# PCB-TLY-JACK-LEDS.net
KiCad netlist of a schematic drawn in EAGLE
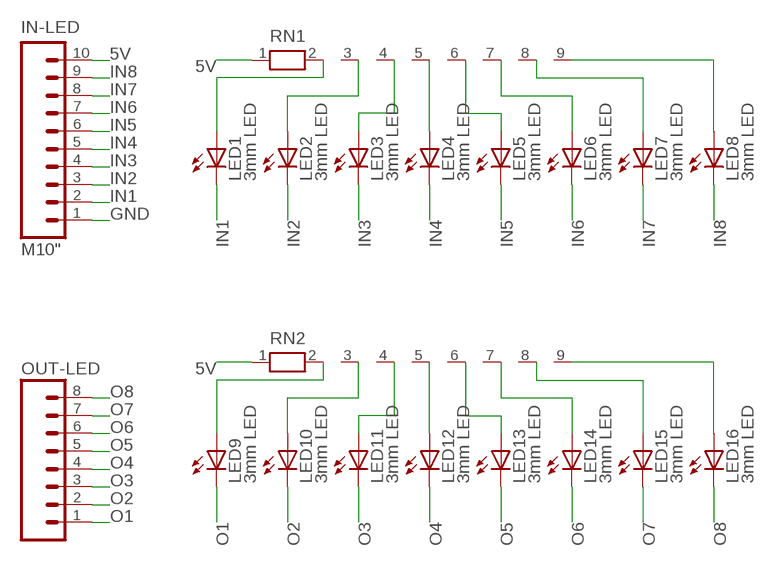
[diagram p0: schematic, sheet 1]

(export (version "E")
  (design (tool "Eeschema 10.0.6"))
  (components
    (comp (ref "IN-LED")
      (value "M10\"")
      (footprint "eagle-import:1X10")
      (libsource (lib "eagle-import") (part "M10{dblquote}"))
    )
    (comp (ref "LED1")
      (value "3mm LED")
      (footprint "eagle-import:LED3MM")
      (libsource (lib "eagle-import") (part "LED3MM"))
    )
    (comp (ref "LED2")
      (value "3mm LED")
      (footprint "eagle-import:LED3MM")
      (libsource (lib "eagle-import") (part "LED3MM"))
    )
    (comp (ref "LED3")
      (value "3mm LED")
      (footprint "eagle-import:LED3MM")
      (libsource (lib "eagle-import") (part "LED3MM"))
    )
    (comp (ref "LED4")
      (value "3mm LED")
      (footprint "eagle-import:LED3MM")
      (libsource (lib "eagle-import") (part "LED3MM"))
    )
    (comp (ref "LED5")
      (value "3mm LED")
      (footprint "eagle-import:LED3MM")
      (libsource (lib "eagle-import") (part "LED3MM"))
    )
    (comp (ref "LED6")
      (value "3mm LED")
      (footprint "eagle-import:LED3MM")
      (libsource (lib "eagle-import") (part "LED3MM"))
    )
    (comp (ref "LED7")
      (value "3mm LED")
      (footprint "eagle-import:LED3MM")
      (libsource (lib "eagle-import") (part "LED3MM"))
    )
    (comp (ref "LED8")
      (value "3mm LED")
      (footprint "eagle-import:LED3MM")
      (libsource (lib "eagle-import") (part "LED3MM"))
    )
    (comp (ref "LED9")
      (value "3mm LED")
      (footprint "eagle-import:LED3MM")
      (libsource (lib "eagle-import") (part "LED3MM"))
    )
    (comp (ref "LED10")
      (value "3mm LED")
      (footprint "eagle-import:LED3MM")
      (libsource (lib "eagle-import") (part "LED3MM"))
    )
    (comp (ref "LED11")
      (value "3mm LED")
      (footprint "eagle-import:LED3MM")
      (libsource (lib "eagle-import") (part "LED3MM"))
    )
    (comp (ref "LED12")
      (value "3mm LED")
      (footprint "eagle-import:LED3MM")
      (libsource (lib "eagle-import") (part "LED3MM"))
    )
    (comp (ref "LED13")
      (value "3mm LED")
      (footprint "eagle-import:LED3MM")
      (libsource (lib "eagle-import") (part "LED3MM"))
    )
    (comp (ref "LED14")
      (value "3mm LED")
      (footprint "eagle-import:LED3MM")
      (libsource (lib "eagle-import") (part "LED3MM"))
    )
    (comp (ref "LED15")
      (value "3mm LED")
      (footprint "eagle-import:LED3MM")
      (libsource (lib "eagle-import") (part "LED3MM"))
    )
    (comp (ref "LED16")
      (value "3mm LED")
      (footprint "eagle-import:LED3MM")
      (libsource (lib "eagle-import") (part "LED3MM"))
    )
    (comp (ref "OUT-LED")
      (value "M081X08")
      (footprint "eagle-import:1X08")
      (libsource (lib "eagle-import") (part "M081X08"))
    )
    (comp (ref "RN1")
      (value "RN08")
      (footprint "eagle-import:RN-9")
      (libsource (lib "eagle-import") (part "RN08"))
    )
    (comp (ref "RN2")
      (value "RN08")
      (footprint "eagle-import:RN-9")
      (libsource (lib "eagle-import") (part "RN08"))
    )
  )
  (nets
    (net (code "1") (name "/5V") (class "Default")
      (node (ref "IN-LED") (pin "10") (pinfunction "10_10") (pintype "passive"))
      (node (ref "RN1") (pin "1") (pinfunction "1_1") (pintype "passive"))
      (node (ref "RN2") (pin "1") (pinfunction "1_1") (pintype "passive"))
    )
    (net (code "2") (name "/GND") (class "Default")
      (node (ref "IN-LED") (pin "1") (pinfunction "1_1") (pintype "passive"))
    )
    (net (code "3") (name "/IN1") (class "Default")
      (node (ref "IN-LED") (pin "2") (pinfunction "2_2") (pintype "passive"))
      (node (ref "LED1") (pin "K") (pinfunction "C_K") (pintype "passive"))
    )
    (net (code "4") (name "/IN2") (class "Default")
      (node (ref "IN-LED") (pin "3") (pinfunction "3_3") (pintype "passive"))
      (node (ref "LED2") (pin "K") (pinfunction "C_K") (pintype "passive"))
    )
    (net (code "5") (name "/IN3") (class "Default")
      (node (ref "IN-LED") (pin "4") (pinfunction "4_4") (pintype "passive"))
      (node (ref "LED3") (pin "K") (pinfunction "C_K") (pintype "passive"))
    )
    (net (code "6") (name "/IN4") (class "Default")
      (node (ref "IN-LED") (pin "5") (pinfunction "5_5") (pintype "passive"))
      (node (ref "LED4") (pin "K") (pinfunction "C_K") (pintype "passive"))
    )
    (net (code "7") (name "/IN5") (class "Default")
      (node (ref "IN-LED") (pin "6") (pinfunction "6_6") (pintype "passive"))
      (node (ref "LED5") (pin "K") (pinfunction "C_K") (pintype "passive"))
    )
    (net (code "8") (name "/IN6") (class "Default")
      (node (ref "IN-LED") (pin "7") (pinfunction "7_7") (pintype "passive"))
      (node (ref "LED6") (pin "K") (pinfunction "C_K") (pintype "passive"))
    )
    (net (code "9") (name "/IN7") (class "Default")
      (node (ref "IN-LED") (pin "8") (pinfunction "8_8") (pintype "passive"))
      (node (ref "LED7") (pin "K") (pinfunction "C_K") (pintype "passive"))
    )
    (net (code "10") (name "/IN8") (class "Default")
      (node (ref "IN-LED") (pin "9") (pinfunction "9_9") (pintype "passive"))
      (node (ref "LED8") (pin "K") (pinfunction "C_K") (pintype "passive"))
    )
    (net (code "11") (name "/O1") (class "Default")
      (node (ref "LED9") (pin "K") (pinfunction "C_K") (pintype "passive"))
      (node (ref "OUT-LED") (pin "1") (pinfunction "1_1") (pintype "passive"))
    )
    (net (code "12") (name "/O2") (class "Default")
      (node (ref "LED10") (pin "K") (pinfunction "C_K") (pintype "passive"))
      (node (ref "OUT-LED") (pin "2") (pinfunction "2_2") (pintype "passive"))
    )
    (net (code "13") (name "/O3") (class "Default")
      (node (ref "LED11") (pin "K") (pinfunction "C_K") (pintype "passive"))
      (node (ref "OUT-LED") (pin "3") (pinfunction "3_3") (pintype "passive"))
    )
    (net (code "14") (name "/O4") (class "Default")
      (node (ref "LED12") (pin "K") (pinfunction "C_K") (pintype "passive"))
      (node (ref "OUT-LED") (pin "4") (pinfunction "4_4") (pintype "passive"))
    )
    (net (code "15") (name "/O5") (class "Default")
      (node (ref "LED13") (pin "K") (pinfunction "C_K") (pintype "passive"))
      (node (ref "OUT-LED") (pin "5") (pinfunction "5_5") (pintype "passive"))
    )
    (net (code "16") (name "/O6") (class "Default")
      (node (ref "LED14") (pin "K") (pinfunction "C_K") (pintype "passive"))
      (node (ref "OUT-LED") (pin "6") (pinfunction "6_6") (pintype "passive"))
    )
    (net (code "17") (name "/O7") (class "Default")
      (node (ref "LED15") (pin "K") (pinfunction "C_K") (pintype "passive"))
      (node (ref "OUT-LED") (pin "7") (pinfunction "7_7") (pintype "passive"))
    )
    (net (code "18") (name "/O8") (class "Default")
      (node (ref "LED16") (pin "K") (pinfunction "C_K") (pintype "passive"))
      (node (ref "OUT-LED") (pin "8") (pinfunction "8_8") (pintype "passive"))
    )
    (net (code "19") (name "Net-(LED1-PadA)") (class "Default")
      (node (ref "LED1") (pin "A") (pinfunction "A_A") (pintype "passive"))
      (node (ref "RN1") (pin "2") (pinfunction "2_2") (pintype "passive"))
    )
    (net (code "20") (name "Net-(LED2-PadA)") (class "Default")
      (node (ref "LED2") (pin "A") (pinfunction "A_A") (pintype "passive"))
      (node (ref "RN1") (pin "3") (pinfunction "3_3") (pintype "passive"))
    )
    (net (code "21") (name "Net-(LED3-PadA)") (class "Default")
      (node (ref "LED3") (pin "A") (pinfunction "A_A") (pintype "passive"))
      (node (ref "RN1") (pin "4") (pinfunction "4_4") (pintype "passive"))
    )
    (net (code "22") (name "Net-(LED4-PadA)") (class "Default")
      (node (ref "LED4") (pin "A") (pinfunction "A_A") (pintype "passive"))
      (node (ref "RN1") (pin "5") (pinfunction "5_5") (pintype "passive"))
    )
    (net (code "23") (name "Net-(LED5-PadA)") (class "Default")
      (node (ref "LED5") (pin "A") (pinfunction "A_A") (pintype "passive"))
      (node (ref "RN1") (pin "6") (pinfunction "6_6") (pintype "passive"))
    )
    (net (code "24") (name "Net-(LED6-PadA)") (class "Default")
      (node (ref "LED6") (pin "A") (pinfunction "A_A") (pintype "passive"))
      (node (ref "RN1") (pin "7") (pinfunction "7_7") (pintype "passive"))
    )
    (net (code "25") (name "Net-(LED7-PadA)") (class "Default")
      (node (ref "LED7") (pin "A") (pinfunction "A_A") (pintype "passive"))
      (node (ref "RN1") (pin "8") (pinfunction "8_8") (pintype "passive"))
    )
    (net (code "26") (name "Net-(LED8-PadA)") (class "Default")
      (node (ref "LED8") (pin "A") (pinfunction "A_A") (pintype "passive"))
      (node (ref "RN1") (pin "9") (pinfunction "9_9") (pintype "passive"))
    )
    (net (code "27") (name "Net-(LED9-PadA)") (class "Default")
      (node (ref "LED9") (pin "A") (pinfunction "A_A") (pintype "passive"))
      (node (ref "RN2") (pin "2") (pinfunction "2_2") (pintype "passive"))
    )
    (net (code "28") (name "Net-(LED10-PadA)") (class "Default")
      (node (ref "LED10") (pin "A") (pinfunction "A_A") (pintype "passive"))
      (node (ref "RN2") (pin "3") (pinfunction "3_3") (pintype "passive"))
    )
    (net (code "29") (name "Net-(LED11-PadA)") (class "Default")
      (node (ref "LED11") (pin "A") (pinfunction "A_A") (pintype "passive"))
      (node (ref "RN2") (pin "4") (pinfunction "4_4") (pintype "passive"))
    )
    (net (code "30") (name "Net-(LED12-PadA)") (class "Default")
      (node (ref "LED12") (pin "A") (pinfunction "A_A") (pintype "passive"))
      (node (ref "RN2") (pin "5") (pinfunction "5_5") (pintype "passive"))
    )
    (net (code "31") (name "Net-(LED13-PadA)") (class "Default")
      (node (ref "LED13") (pin "A") (pinfunction "A_A") (pintype "passive"))
      (node (ref "RN2") (pin "6") (pinfunction "6_6") (pintype "passive"))
    )
    (net (code "32") (name "Net-(LED14-PadA)") (class "Default")
      (node (ref "LED14") (pin "A") (pinfunction "A_A") (pintype "passive"))
      (node (ref "RN2") (pin "7") (pinfunction "7_7") (pintype "passive"))
    )
    (net (code "33") (name "Net-(LED15-PadA)") (class "Default")
      (node (ref "LED15") (pin "A") (pinfunction "A_A") (pintype "passive"))
      (node (ref "RN2") (pin "8") (pinfunction "8_8") (pintype "passive"))
    )
    (net (code "34") (name "Net-(LED16-PadA)") (class "Default")
      (node (ref "LED16") (pin "A") (pinfunction "A_A") (pintype "passive"))
      (node (ref "RN2") (pin "9") (pinfunction "9_9") (pintype "passive"))
    )
  )
)
